# ADS131A04.net
KiCad netlist of a schematic drawn in Altium Designer
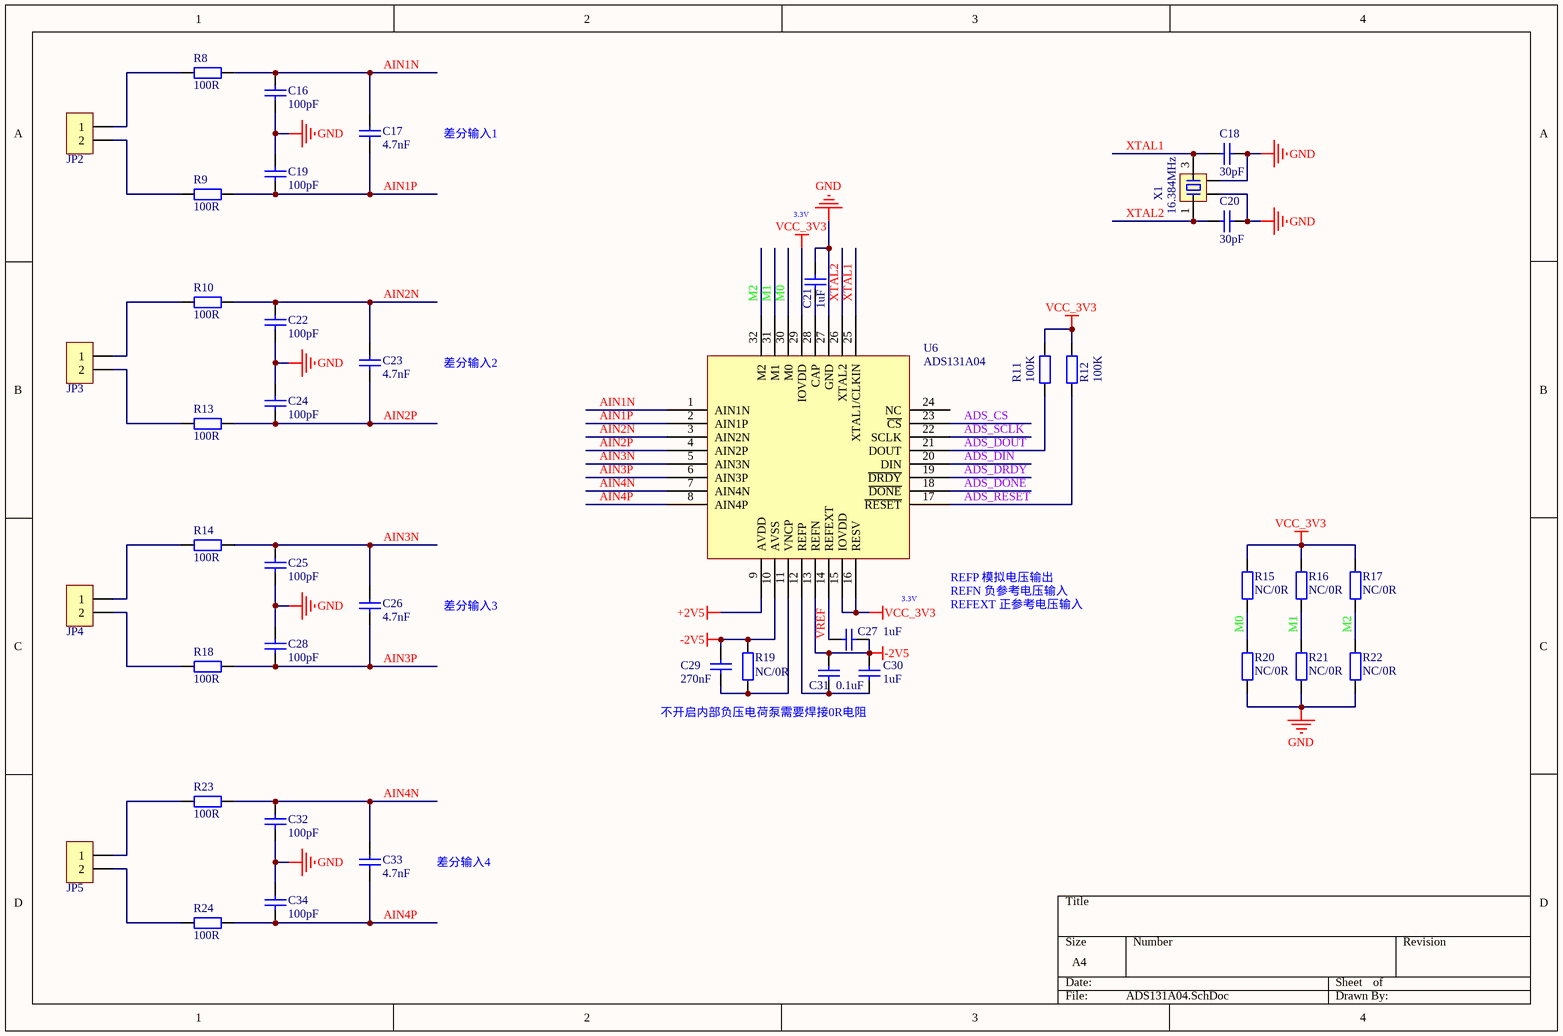
[diagram p0: ADS131A04.SchDoc]

(export (version "E")
  (design (tool "Eeschema 10.0.6"))
  (components
    (comp (ref "C16")
      (value "100pF")
      (footprint "C0402_L")
      (description "贴片电容")
      (libsource (lib "0.1 - 电阻-电容-电感-晶振-晶体-磁珠-电位器") (part "C"))
    )
    (comp (ref "C17")
      (value "4.7nF")
      (footprint "C0402_L")
      (description "贴片电容")
      (libsource (lib "0.1 - 电阻-电容-电感-晶振-晶体-磁珠-电位器") (part "C"))
    )
    (comp (ref "C18")
      (value "30pF")
      (footprint "C0402_L")
      (description "贴片电容")
      (libsource (lib "0.1 - 电阻-电容-电感-晶振-晶体-磁珠-电位器") (part "C"))
    )
    (comp (ref "C19")
      (value "100pF")
      (footprint "C0402_L")
      (description "贴片电容")
      (libsource (lib "0.1 - 电阻-电容-电感-晶振-晶体-磁珠-电位器") (part "C"))
    )
    (comp (ref "C20")
      (value "30pF")
      (footprint "C0402_L")
      (description "贴片电容")
      (libsource (lib "0.1 - 电阻-电容-电感-晶振-晶体-磁珠-电位器") (part "C"))
    )
    (comp (ref "C21")
      (value "1uF")
      (footprint "C0402_L")
      (description "贴片电容")
      (libsource (lib "0.1 - 电阻-电容-电感-晶振-晶体-磁珠-电位器") (part "C"))
    )
    (comp (ref "C22")
      (value "100pF")
      (footprint "C0402_L")
      (description "贴片电容")
      (libsource (lib "0.1 - 电阻-电容-电感-晶振-晶体-磁珠-电位器") (part "C"))
    )
    (comp (ref "C23")
      (value "4.7nF")
      (footprint "C0402_L")
      (description "贴片电容")
      (libsource (lib "0.1 - 电阻-电容-电感-晶振-晶体-磁珠-电位器") (part "C"))
    )
    (comp (ref "C24")
      (value "100pF")
      (footprint "C0402_L")
      (description "贴片电容")
      (libsource (lib "0.1 - 电阻-电容-电感-晶振-晶体-磁珠-电位器") (part "C"))
    )
    (comp (ref "C25")
      (value "100pF")
      (footprint "C0402_L")
      (description "贴片电容")
      (libsource (lib "0.1 - 电阻-电容-电感-晶振-晶体-磁珠-电位器") (part "C"))
    )
    (comp (ref "C26")
      (value "4.7nF")
      (footprint "C0402_L")
      (description "贴片电容")
      (libsource (lib "0.1 - 电阻-电容-电感-晶振-晶体-磁珠-电位器") (part "C"))
    )
    (comp (ref "C27")
      (value "1uF")
      (footprint "C0402_L")
      (description "贴片电容")
      (libsource (lib "0.1 - 电阻-电容-电感-晶振-晶体-磁珠-电位器") (part "C"))
    )
    (comp (ref "C28")
      (value "100pF")
      (footprint "C0402_L")
      (description "贴片电容")
      (libsource (lib "0.1 - 电阻-电容-电感-晶振-晶体-磁珠-电位器") (part "C"))
    )
    (comp (ref "C29")
      (value "270nF")
      (footprint "C0402_L")
      (description "贴片电容")
      (libsource (lib "0.1 - 电阻-电容-电感-晶振-晶体-磁珠-电位器") (part "C"))
    )
    (comp (ref "C30")
      (value "1uF")
      (footprint "C0402_L")
      (description "贴片电容")
      (libsource (lib "0.1 - 电阻-电容-电感-晶振-晶体-磁珠-电位器") (part "C"))
    )
    (comp (ref "C31")
      (value "0.1uF")
      (footprint "C0402_L")
      (description "贴片电容")
      (libsource (lib "0.1 - 电阻-电容-电感-晶振-晶体-磁珠-电位器") (part "C"))
    )
    (comp (ref "C32")
      (value "100pF")
      (footprint "C0402_L")
      (description "贴片电容")
      (libsource (lib "0.1 - 电阻-电容-电感-晶振-晶体-磁珠-电位器") (part "C"))
    )
    (comp (ref "C33")
      (value "4.7nF")
      (footprint "C0402_L")
      (description "贴片电容")
      (libsource (lib "0.1 - 电阻-电容-电感-晶振-晶体-磁珠-电位器") (part "C"))
    )
    (comp (ref "C34")
      (value "100pF")
      (footprint "C0402_L")
      (description "贴片电容")
      (libsource (lib "0.1 - 电阻-电容-电感-晶振-晶体-磁珠-电位器") (part "C"))
    )
    (comp (ref "JP2")
      (value "HDR-1X2")
      (footprint "HDR2.54-WS-2P")
      (description "2P接插件")
      (libsource (lib "5.5 - 2.54mm(100mil)连接器(XH2.54)") (part "Header 2"))
    )
    (comp (ref "JP3")
      (value "HDR-1X2")
      (footprint "HDR2.54-WS-2P")
      (description "2P接插件")
      (libsource (lib "5.5 - 2.54mm(100mil)连接器(XH2.54)") (part "Header 2"))
    )
    (comp (ref "JP4")
      (value "HDR-1X2")
      (footprint "HDR2.54-WS-2P")
      (description "2P接插件")
      (libsource (lib "5.5 - 2.54mm(100mil)连接器(XH2.54)") (part "Header 2"))
    )
    (comp (ref "JP5")
      (value "HDR-1X2")
      (footprint "HDR2.54-WS-2P")
      (description "2P接插件")
      (libsource (lib "5.5 - 2.54mm(100mil)连接器(XH2.54)") (part "Header 2"))
    )
    (comp (ref "R8")
      (value "100R")
      (footprint "R0402_L")
      (description "贴片电阻")
      (libsource (lib "0.1 - 电阻-电容-电感-晶振-晶体-磁珠-电位器") (part "R"))
    )
    (comp (ref "R9")
      (value "100R")
      (footprint "R0402_L")
      (description "贴片电阻")
      (libsource (lib "0.1 - 电阻-电容-电感-晶振-晶体-磁珠-电位器") (part "R"))
    )
    (comp (ref "R10")
      (value "100R")
      (footprint "R0402_L")
      (description "贴片电阻")
      (libsource (lib "0.1 - 电阻-电容-电感-晶振-晶体-磁珠-电位器") (part "R"))
    )
    (comp (ref "R11")
      (value "100K")
      (footprint "R0402_L")
      (description "贴片电阻")
      (libsource (lib "0.1 - 电阻-电容-电感-晶振-晶体-磁珠-电位器") (part "R"))
    )
    (comp (ref "R12")
      (value "100K")
      (footprint "R0402_L")
      (description "贴片电阻")
      (libsource (lib "0.1 - 电阻-电容-电感-晶振-晶体-磁珠-电位器") (part "R"))
    )
    (comp (ref "R13")
      (value "100R")
      (footprint "R0402_L")
      (description "贴片电阻")
      (libsource (lib "0.1 - 电阻-电容-电感-晶振-晶体-磁珠-电位器") (part "R"))
    )
    (comp (ref "R14")
      (value "100R")
      (footprint "R0402_L")
      (description "贴片电阻")
      (libsource (lib "0.1 - 电阻-电容-电感-晶振-晶体-磁珠-电位器") (part "R"))
    )
    (comp (ref "R15")
      (value "NC/0R")
      (footprint "R0402_L")
      (description "贴片电阻")
      (libsource (lib "0.1 - 电阻-电容-电感-晶振-晶体-磁珠-电位器") (part "R"))
    )
    (comp (ref "R16")
      (value "NC/0R")
      (footprint "R0402_L")
      (description "贴片电阻")
      (libsource (lib "0.1 - 电阻-电容-电感-晶振-晶体-磁珠-电位器") (part "R"))
    )
    (comp (ref "R17")
      (value "NC/0R")
      (footprint "R0402_L")
      (description "贴片电阻")
      (libsource (lib "0.1 - 电阻-电容-电感-晶振-晶体-磁珠-电位器") (part "R"))
    )
    (comp (ref "R18")
      (value "100R")
      (footprint "R0402_L")
      (description "贴片电阻")
      (libsource (lib "0.1 - 电阻-电容-电感-晶振-晶体-磁珠-电位器") (part "R"))
    )
    (comp (ref "R19")
      (value "NC/0R")
      (footprint "R0402_L")
      (description "贴片电阻")
      (libsource (lib "0.1 - 电阻-电容-电感-晶振-晶体-磁珠-电位器") (part "R"))
    )
    (comp (ref "R20")
      (value "NC/0R")
      (footprint "R0402_L")
      (description "贴片电阻")
      (libsource (lib "0.1 - 电阻-电容-电感-晶振-晶体-磁珠-电位器") (part "R"))
    )
    (comp (ref "R21")
      (value "NC/0R")
      (footprint "R0402_L")
      (description "贴片电阻")
      (libsource (lib "0.1 - 电阻-电容-电感-晶振-晶体-磁珠-电位器") (part "R"))
    )
    (comp (ref "R22")
      (value "NC/0R")
      (footprint "R0402_L")
      (description "贴片电阻")
      (libsource (lib "0.1 - 电阻-电容-电感-晶振-晶体-磁珠-电位器") (part "R"))
    )
    (comp (ref "R23")
      (value "100R")
      (footprint "R0402_L")
      (description "贴片电阻")
      (libsource (lib "0.1 - 电阻-电容-电感-晶振-晶体-磁珠-电位器") (part "R"))
    )
    (comp (ref "R24")
      (value "100R")
      (footprint "R0402_L")
      (description "贴片电阻")
      (libsource (lib "0.1 - 电阻-电容-电感-晶振-晶体-磁珠-电位器") (part "R"))
    )
    (comp (ref "U6")
      (value "ADS131A04")
      (footprint "TQFP32 5x5_L")
      (description "4通道差分24位ADC")
      (libsource (lib "USER_Lib") (part "ADS131A04"))
    )
    (comp (ref "X1")
      (value "16.384MHz")
      (footprint "XTAL-3225-4P")
      (description "4脚无源晶振(谐振器）")
      (libsource (lib "0.1 - 电阻-电容-电感-晶振-晶体-磁珠-电位器") (part "XTAL-4P"))
    )
  )
  (nets
    (net (code "1") (name "+2V5") (class "Default")
      (node (ref "U6") (pin "9") (pinfunction "AVDD_9") (pintype "passive"))
    )
    (net (code "2") (name "-2V5") (class "Default")
      (node (ref "C27") (pin "2") (pinfunction "2_2") (pintype "passive"))
      (node (ref "C29") (pin "2") (pinfunction "2_2") (pintype "passive"))
      (node (ref "C30") (pin "2") (pinfunction "2_2") (pintype "passive"))
      (node (ref "C31") (pin "2") (pinfunction "2_2") (pintype "passive"))
      (node (ref "R19") (pin "2") (pinfunction "2_2") (pintype "passive"))
      (node (ref "U6") (pin "10") (pinfunction "AVSS_10") (pintype "passive"))
      (node (ref "U6") (pin "13") (pinfunction "REFN_13") (pintype "passive"))
    )
    (net (code "3") (name "/ADS_CS") (class "Default")
      (node (ref "U6") (pin "23") (pinfunction "~{CS}_23") (pintype "passive"))
    )
    (net (code "4") (name "/ADS_DIN") (class "Default")
      (node (ref "U6") (pin "20") (pinfunction "DIN_20") (pintype "passive"))
    )
    (net (code "5") (name "/ADS_DONE") (class "Default")
      (node (ref "U6") (pin "18") (pinfunction "~{DONE}_18") (pintype "passive"))
    )
    (net (code "6") (name "/ADS_DOUT") (class "Default")
      (node (ref "R11") (pin "1") (pinfunction "1_1") (pintype "passive"))
      (node (ref "U6") (pin "21") (pinfunction "DOUT_21") (pintype "passive"))
    )
    (net (code "7") (name "/ADS_DRDY") (class "Default")
      (node (ref "U6") (pin "19") (pinfunction "~{DRDY}_19") (pintype "passive"))
    )
    (net (code "8") (name "/ADS_RESET") (class "Default")
      (node (ref "R12") (pin "1") (pinfunction "1_1") (pintype "passive"))
      (node (ref "U6") (pin "17") (pinfunction "~{RESET}_17") (pintype "passive"))
    )
    (net (code "9") (name "/ADS_SCLK") (class "Default")
      (node (ref "U6") (pin "22") (pinfunction "SCLK_22") (pintype "passive"))
    )
    (net (code "10") (name "/AIN1N") (class "Default")
      (node (ref "C16") (pin "2") (pinfunction "2_2") (pintype "passive"))
      (node (ref "C17") (pin "2") (pinfunction "2_2") (pintype "passive"))
      (node (ref "R8") (pin "2") (pinfunction "2_2") (pintype "passive"))
      (node (ref "U6") (pin "1") (pinfunction "AIN1N_1") (pintype "passive"))
    )
    (net (code "11") (name "/AIN1P") (class "Default")
      (node (ref "C17") (pin "1") (pinfunction "1_1") (pintype "passive"))
      (node (ref "C19") (pin "1") (pinfunction "1_1") (pintype "passive"))
      (node (ref "R9") (pin "2") (pinfunction "2_2") (pintype "passive"))
      (node (ref "U6") (pin "2") (pinfunction "AIN1P_2") (pintype "passive"))
    )
    (net (code "12") (name "/AIN2N") (class "Default")
      (node (ref "C22") (pin "2") (pinfunction "2_2") (pintype "passive"))
      (node (ref "C23") (pin "2") (pinfunction "2_2") (pintype "passive"))
      (node (ref "R10") (pin "2") (pinfunction "2_2") (pintype "passive"))
      (node (ref "U6") (pin "3") (pinfunction "AIN2N_3") (pintype "passive"))
    )
    (net (code "13") (name "/AIN2P") (class "Default")
      (node (ref "C23") (pin "1") (pinfunction "1_1") (pintype "passive"))
      (node (ref "C24") (pin "1") (pinfunction "1_1") (pintype "passive"))
      (node (ref "R13") (pin "2") (pinfunction "2_2") (pintype "passive"))
      (node (ref "U6") (pin "4") (pinfunction "AIN2P_4") (pintype "passive"))
    )
    (net (code "14") (name "/AIN3N") (class "Default")
      (node (ref "C25") (pin "2") (pinfunction "2_2") (pintype "passive"))
      (node (ref "C26") (pin "2") (pinfunction "2_2") (pintype "passive"))
      (node (ref "R14") (pin "2") (pinfunction "2_2") (pintype "passive"))
      (node (ref "U6") (pin "5") (pinfunction "AIN3N_5") (pintype "passive"))
    )
    (net (code "15") (name "/AIN3P") (class "Default")
      (node (ref "C26") (pin "1") (pinfunction "1_1") (pintype "passive"))
      (node (ref "C28") (pin "1") (pinfunction "1_1") (pintype "passive"))
      (node (ref "R18") (pin "2") (pinfunction "2_2") (pintype "passive"))
      (node (ref "U6") (pin "6") (pinfunction "AIN3P_6") (pintype "passive"))
    )
    (net (code "16") (name "/AIN4N") (class "Default")
      (node (ref "C32") (pin "2") (pinfunction "2_2") (pintype "passive"))
      (node (ref "C33") (pin "2") (pinfunction "2_2") (pintype "passive"))
      (node (ref "R23") (pin "2") (pinfunction "2_2") (pintype "passive"))
      (node (ref "U6") (pin "7") (pinfunction "AIN4N_7") (pintype "passive"))
    )
    (net (code "17") (name "/AIN4P") (class "Default")
      (node (ref "C33") (pin "1") (pinfunction "1_1") (pintype "passive"))
      (node (ref "C34") (pin "1") (pinfunction "1_1") (pintype "passive"))
      (node (ref "R24") (pin "2") (pinfunction "2_2") (pintype "passive"))
      (node (ref "U6") (pin "8") (pinfunction "AIN4P_8") (pintype "passive"))
    )
    (net (code "18") (name "/M0") (class "Default")
      (node (ref "R15") (pin "1") (pinfunction "1_1") (pintype "passive"))
      (node (ref "R20") (pin "2") (pinfunction "2_2") (pintype "passive"))
      (node (ref "U6") (pin "30") (pinfunction "M0_30") (pintype "passive"))
    )
    (net (code "19") (name "/M1") (class "Default")
      (node (ref "R16") (pin "1") (pinfunction "1_1") (pintype "passive"))
      (node (ref "R21") (pin "2") (pinfunction "2_2") (pintype "passive"))
      (node (ref "U6") (pin "31") (pinfunction "M1_31") (pintype "passive"))
    )
    (net (code "20") (name "/M2") (class "Default")
      (node (ref "R17") (pin "1") (pinfunction "1_1") (pintype "passive"))
      (node (ref "R22") (pin "2") (pinfunction "2_2") (pintype "passive"))
      (node (ref "U6") (pin "32") (pinfunction "M2_32") (pintype "passive"))
    )
    (net (code "21") (name "/VREF") (class "Default")
      (node (ref "C27") (pin "1") (pinfunction "1_1") (pintype "passive"))
      (node (ref "U6") (pin "14") (pinfunction "REFEXT_14") (pintype "passive"))
    )
    (net (code "22") (name "/XTAL1") (class "Default")
      (node (ref "C18") (pin "1") (pinfunction "1_1") (pintype "passive"))
      (node (ref "U6") (pin "25") (pinfunction "XTAL1/CLKIN_25") (pintype "passive"))
      (node (ref "X1") (pin "3") (pinfunction "3_3") (pintype "passive"))
    )
    (net (code "23") (name "/XTAL2") (class "Default")
      (node (ref "C20") (pin "1") (pinfunction "1_1") (pintype "passive"))
      (node (ref "U6") (pin "26") (pinfunction "XTAL2_26") (pintype "passive"))
      (node (ref "X1") (pin "1") (pinfunction "1_1") (pintype "passive"))
    )
    (net (code "24") (name "GND") (class "Default")
      (node (ref "C16") (pin "1") (pinfunction "1_1") (pintype "passive"))
      (node (ref "C18") (pin "2") (pinfunction "2_2") (pintype "passive"))
      (node (ref "C19") (pin "2") (pinfunction "2_2") (pintype "passive"))
      (node (ref "C20") (pin "2") (pinfunction "2_2") (pintype "passive"))
      (node (ref "C21") (pin "2") (pinfunction "2_2") (pintype "passive"))
      (node (ref "C22") (pin "1") (pinfunction "1_1") (pintype "passive"))
      (node (ref "C24") (pin "2") (pinfunction "2_2") (pintype "passive"))
      (node (ref "C25") (pin "1") (pinfunction "1_1") (pintype "passive"))
      (node (ref "C28") (pin "2") (pinfunction "2_2") (pintype "passive"))
      (node (ref "C32") (pin "1") (pinfunction "1_1") (pintype "passive"))
      (node (ref "C34") (pin "2") (pinfunction "2_2") (pintype "passive"))
      (node (ref "R20") (pin "1") (pinfunction "1_1") (pintype "passive"))
      (node (ref "R21") (pin "1") (pinfunction "1_1") (pintype "passive"))
      (node (ref "R22") (pin "1") (pinfunction "1_1") (pintype "passive"))
      (node (ref "U6") (pin "27") (pinfunction "GND_27") (pintype "passive"))
      (node (ref "X1") (pin "2") (pinfunction "2_2") (pintype "passive"))
      (node (ref "X1") (pin "4") (pinfunction "4_4") (pintype "passive"))
    )
    (net (code "25") (name "Net-(JP2-Pad1)") (class "Default")
      (node (ref "JP2") (pin "1") (pinfunction "1_1") (pintype "passive"))
      (node (ref "R8") (pin "1") (pinfunction "1_1") (pintype "passive"))
    )
    (net (code "26") (name "Net-(JP2-Pad2)") (class "Default")
      (node (ref "JP2") (pin "2") (pinfunction "2_2") (pintype "passive"))
      (node (ref "R9") (pin "1") (pinfunction "1_1") (pintype "passive"))
    )
    (net (code "27") (name "Net-(JP3-Pad1)") (class "Default")
      (node (ref "JP3") (pin "1") (pinfunction "1_1") (pintype "passive"))
      (node (ref "R10") (pin "1") (pinfunction "1_1") (pintype "passive"))
    )
    (net (code "28") (name "Net-(JP3-Pad2)") (class "Default")
      (node (ref "JP3") (pin "2") (pinfunction "2_2") (pintype "passive"))
      (node (ref "R13") (pin "1") (pinfunction "1_1") (pintype "passive"))
    )
    (net (code "29") (name "Net-(JP4-Pad1)") (class "Default")
      (node (ref "JP4") (pin "1") (pinfunction "1_1") (pintype "passive"))
      (node (ref "R14") (pin "1") (pinfunction "1_1") (pintype "passive"))
    )
    (net (code "30") (name "Net-(JP4-Pad2)") (class "Default")
      (node (ref "JP4") (pin "2") (pinfunction "2_2") (pintype "passive"))
      (node (ref "R18") (pin "1") (pinfunction "1_1") (pintype "passive"))
    )
    (net (code "31") (name "Net-(JP5-Pad1)") (class "Default")
      (node (ref "JP5") (pin "1") (pinfunction "1_1") (pintype "passive"))
      (node (ref "R23") (pin "1") (pinfunction "1_1") (pintype "passive"))
    )
    (net (code "32") (name "Net-(JP5-Pad2)") (class "Default")
      (node (ref "JP5") (pin "2") (pinfunction "2_2") (pintype "passive"))
      (node (ref "R24") (pin "1") (pinfunction "1_1") (pintype "passive"))
    )
    (net (code "33") (name "Net-(U6-CAP)") (class "Default")
      (node (ref "C21") (pin "1") (pinfunction "1_1") (pintype "passive"))
      (node (ref "U6") (pin "28") (pinfunction "CAP_28") (pintype "passive"))
    )
    (net (code "34") (name "Net-(U6-REFP)") (class "Default")
      (node (ref "C30") (pin "1") (pinfunction "1_1") (pintype "passive"))
      (node (ref "C31") (pin "1") (pinfunction "1_1") (pintype "passive"))
      (node (ref "U6") (pin "12") (pinfunction "REFP_12") (pintype "passive"))
    )
    (net (code "35") (name "Net-(U6-VNCP)") (class "Default")
      (node (ref "C29") (pin "1") (pinfunction "1_1") (pintype "passive"))
      (node (ref "R19") (pin "1") (pinfunction "1_1") (pintype "passive"))
      (node (ref "U6") (pin "11") (pinfunction "VNCP_11") (pintype "passive"))
    )
    (net (code "36") (name "VCC_3V3") (class "Default")
      (node (ref "R11") (pin "2") (pinfunction "2_2") (pintype "passive"))
      (node (ref "R12") (pin "2") (pinfunction "2_2") (pintype "passive"))
      (node (ref "R15") (pin "2") (pinfunction "2_2") (pintype "passive"))
      (node (ref "R16") (pin "2") (pinfunction "2_2") (pintype "passive"))
      (node (ref "R17") (pin "2") (pinfunction "2_2") (pintype "passive"))
      (node (ref "U6") (pin "15") (pinfunction "IOVDD_15") (pintype "passive"))
      (node (ref "U6") (pin "16") (pinfunction "RESV_16") (pintype "passive"))
      (node (ref "U6") (pin "29") (pinfunction "IOVDD_29") (pintype "passive"))
    )
    (net (code "37") (name "unconnected-(U6-NC-Pad24)") (class "Default")
      (node (ref "U6") (pin "24") (pinfunction "NC_24") (pintype "passive"))
    )
  )
)
